# Power_TimerEvents.net
KiCad netlist of a schematic drawn in Altium Designer
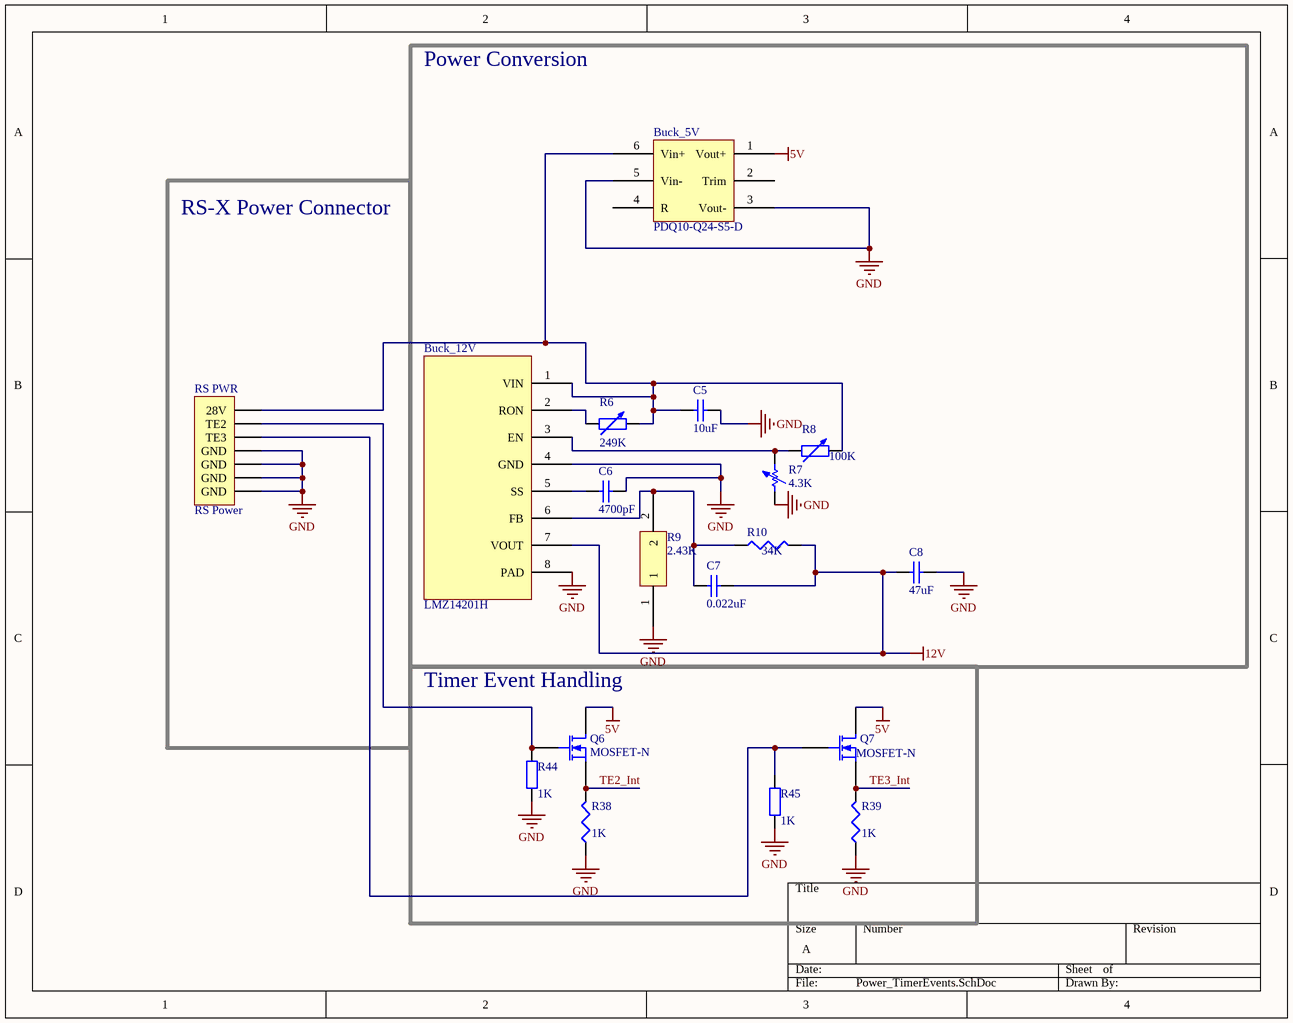
[diagram p0: Power_TimerEvents.SchDoc]

(export (version "E")
  (design (tool "Eeschema 10.0.6"))
  (components
    (comp (ref "Buck_5V")
      (value "PDQ10-Q24-S5-D")
      (footprint "buck_5V")
      (libsource (lib "buck_5V") (part "buck_5V"))
    )
    (comp (ref "Buck_12V")
      (value "LMZ14201H")
      (footprint "LMZ1420")
      (libsource (lib "LMZ1420XX") (part "Component_1"))
    )
    (comp (ref "C5")
      (value "10uF")
      (footprint "C1206")
      (description "Capacitor (Semiconductor SIM Model)")
      (fields (field (name "PUBLISHER") "Altium Limited"))
      (libsource (lib "Miscellaneous Devices") (part "Cap Semi"))
    )
    (comp (ref "C6")
      (value "4700pF")
      (footprint "1608[0603]")
      (description "Capacitor (Semiconductor SIM Model)")
      (fields (field (name "PUBLISHER") "Altium Limited"))
      (libsource (lib "Miscellaneous Devices") (part "Cap Semi"))
    )
    (comp (ref "C7")
      (value "0.022uF")
      (footprint "1608[0603]")
      (description "Capacitor (Semiconductor SIM Model)")
      (fields (field (name "PUBLISHER") "Altium Limited"))
      (libsource (lib "Miscellaneous Devices") (part "Cap Semi"))
    )
    (comp (ref "C8")
      (value "47uF")
      (footprint "C1206")
      (description "Capacitor (Semiconductor SIM Model)")
      (fields (field (name "PUBLISHER") "Altium Limited"))
      (libsource (lib "Miscellaneous Devices") (part "Cap Semi"))
    )
    (comp (ref "Q6")
      (value "MOSFET-N")
      (footprint "E3")
      (description "N-Channel MOSFET")
      (fields (field (name "PUBLISHER") "Altium Limited"))
      (libsource (lib "Miscellaneous Devices") (part "MOSFET-N"))
    )
    (comp (ref "Q7")
      (value "MOSFET-N")
      (footprint "E3")
      (description "N-Channel MOSFET")
      (fields (field (name "PUBLISHER") "Altium Limited"))
      (libsource (lib "Miscellaneous Devices") (part "MOSFET-N"))
    )
    (comp (ref "R6")
      (value "249K")
      (footprint "AXIAL-0.6")
      (description "Variable Resistor")
      (fields (field (name "PUBLISHER") "Altium Limited"))
      (libsource (lib "Miscellaneous Devices") (part "Res Adj2"))
    )
    (comp (ref "R7")
      (value "4.3K")
      (footprint "AXIAL-0.7")
      (description "Variable Resistor")
      (fields (field (name "PUBLISHER") "Altium Limited"))
      (libsource (lib "Miscellaneous Devices") (part "Res Adj1"))
    )
    (comp (ref "R8")
      (value "100K")
      (footprint "AXIAL-0.6")
      (description "Variable Resistor")
      (fields (field (name "PUBLISHER") "Altium Limited"))
      (libsource (lib "Miscellaneous Devices") (part "Res Adj2"))
    )
    (comp (ref "R9") (value "2.43K") (footprint "smd_R9") (libsource (lib "smd_R9_34K") (part "smd_R9")))
    (comp (ref "R10")
      (value "34K")
      (footprint "12Z-2010")
      (description "Resistor")
      (fields (field (name "PUBLISHER") "Altium Limited"))
      (libsource (lib "Miscellaneous Devices") (part "Res3"))
    )
    (comp (ref "R38")
      (value "1K")
      (footprint "J1-0603")
      (description "Resistor")
      (fields (field (name "PUBLISHER") "Altium Limited"))
      (libsource (lib "Miscellaneous Devices") (part "Res3"))
    )
    (comp (ref "R39")
      (value "1K")
      (footprint "J1-0603")
      (description "Resistor")
      (fields (field (name "PUBLISHER") "Altium Limited"))
      (libsource (lib "Miscellaneous Devices") (part "Res3"))
    )
    (comp (ref "R44")
      (value "1K")
      (footprint "AXIAL-0.4")
      (description "Resistor")
      (fields (field (name "PUBLISHER") "Altium Limited"))
      (libsource (lib "Miscellaneous Devices") (part "Res2"))
    )
    (comp (ref "R45")
      (value "1K")
      (footprint "AXIAL-0.4")
      (description "Resistor")
      (fields (field (name "PUBLISHER") "Altium Limited"))
      (libsource (lib "Miscellaneous Devices") (part "Res2"))
    )
    (comp (ref "RS PWR")
      (value "RS Power")
      (footprint "HDR1X7")
      (description "Header, 7-Pin")
      (fields (field (name "PUBLISHER") "Altium Limited"))
      (libsource (lib "Miscellaneous Connectors") (part "Header 7"))
    )
  )
  (nets
    (net (code "1") (name "/TE2_Int") (class "Default")
      (node (ref "Q6") (pin "3") (pinfunction "S_3") (pintype "passive"))
      (node (ref "R38") (pin "2") (pinfunction "2_2") (pintype "passive"))
    )
    (net (code "2") (name "/TE3_Int") (class "Default")
      (node (ref "Q7") (pin "3") (pinfunction "S_3") (pintype "passive"))
      (node (ref "R39") (pin "2") (pinfunction "2_2") (pintype "passive"))
    )
    (net (code "3") (name "5V") (class "Default")
      (node (ref "Buck_5V") (pin "1") (pinfunction "Vout+_1") (pintype "passive"))
      (node (ref "Q6") (pin "1") (pinfunction "D_1") (pintype "passive"))
      (node (ref "Q7") (pin "1") (pinfunction "D_1") (pintype "passive"))
    )
    (net (code "4") (name "12V") (class "Default")
      (node (ref "Buck_12V") (pin "7") (pinfunction "VOUT_7") (pintype "passive"))
      (node (ref "C7") (pin "2") (pinfunction "2_2") (pintype "passive"))
      (node (ref "C8") (pin "1") (pinfunction "1_1") (pintype "passive"))
      (node (ref "R10") (pin "2") (pinfunction "2_2") (pintype "passive"))
    )
    (net (code "5") (name "GND") (class "Default")
      (node (ref "Buck_12V") (pin "4") (pinfunction "GND_4") (pintype "passive"))
      (node (ref "Buck_12V") (pin "8") (pinfunction "PAD_8") (pintype "passive"))
      (node (ref "Buck_5V") (pin "3") (pinfunction "Vout-_3") (pintype "passive"))
      (node (ref "Buck_5V") (pin "5") (pinfunction "Vin-_5") (pintype "passive"))
      (node (ref "C5") (pin "2") (pinfunction "2_2") (pintype "passive"))
      (node (ref "C6") (pin "2") (pinfunction "2_2") (pintype "passive"))
      (node (ref "C8") (pin "2") (pinfunction "2_2") (pintype "passive"))
      (node (ref "R38") (pin "1") (pinfunction "1_1") (pintype "passive"))
      (node (ref "R39") (pin "1") (pinfunction "1_1") (pintype "passive"))
      (node (ref "R44") (pin "1") (pinfunction "1_1") (pintype "passive"))
      (node (ref "R45") (pin "1") (pinfunction "1_1") (pintype "passive"))
      (node (ref "R7") (pin "1") (pinfunction "1_1") (pintype "passive"))
      (node (ref "R9") (pin "1") (pinfunction "1_1") (pintype "passive"))
      (node (ref "RS PWR") (pin "4") (pinfunction "GND_4") (pintype "passive"))
      (node (ref "RS PWR") (pin "5") (pinfunction "GND_5") (pintype "passive"))
      (node (ref "RS PWR") (pin "6") (pinfunction "GND_6") (pintype "passive"))
      (node (ref "RS PWR") (pin "7") (pinfunction "GND_7") (pintype "passive"))
    )
    (net (code "6") (name "Net-(Buck_12V-EN)") (class "Default")
      (node (ref "Buck_12V") (pin "3") (pinfunction "EN_3") (pintype "passive"))
      (node (ref "R7") (pin "2") (pinfunction "2_2") (pintype "passive"))
      (node (ref "R8") (pin "1") (pinfunction "1_1") (pintype "passive"))
    )
    (net (code "7") (name "Net-(Buck_12V-FB)") (class "Default")
      (node (ref "Buck_12V") (pin "6") (pinfunction "FB_6") (pintype "passive"))
      (node (ref "C7") (pin "1") (pinfunction "1_1") (pintype "passive"))
      (node (ref "R10") (pin "1") (pinfunction "1_1") (pintype "passive"))
      (node (ref "R9") (pin "2") (pinfunction "2_2") (pintype "passive"))
    )
    (net (code "8") (name "Net-(Buck_12V-RON)") (class "Default")
      (node (ref "Buck_12V") (pin "2") (pinfunction "RON_2") (pintype "passive"))
      (node (ref "R6") (pin "1") (pinfunction "1_1") (pintype "passive"))
    )
    (net (code "9") (name "Net-(Buck_12V-SS)") (class "Default")
      (node (ref "Buck_12V") (pin "5") (pinfunction "SS_5") (pintype "passive"))
      (node (ref "C6") (pin "1") (pinfunction "1_1") (pintype "passive"))
    )
    (net (code "10") (name "Net-(Buck_12V-VIN)") (class "Default")
      (node (ref "Buck_12V") (pin "1") (pinfunction "VIN_1") (pintype "passive"))
      (node (ref "Buck_5V") (pin "6") (pinfunction "Vin+_6") (pintype "passive"))
      (node (ref "C5") (pin "1") (pinfunction "1_1") (pintype "passive"))
      (node (ref "R6") (pin "2") (pinfunction "2_2") (pintype "passive"))
      (node (ref "R8") (pin "2") (pinfunction "2_2") (pintype "passive"))
      (node (ref "RS PWR") (pin "1") (pinfunction "28V_1") (pintype "passive"))
    )
    (net (code "11") (name "Net-(Q6-G)") (class "Default")
      (node (ref "Q6") (pin "2") (pinfunction "G_2") (pintype "passive"))
      (node (ref "R44") (pin "2") (pinfunction "2_2") (pintype "passive"))
      (node (ref "RS PWR") (pin "2") (pinfunction "TE2_2") (pintype "passive"))
    )
    (net (code "12") (name "Net-(Q7-G)") (class "Default")
      (node (ref "Q7") (pin "2") (pinfunction "G_2") (pintype "passive"))
      (node (ref "R45") (pin "2") (pinfunction "2_2") (pintype "passive"))
      (node (ref "RS PWR") (pin "3") (pinfunction "TE3_3") (pintype "passive"))
    )
    (net (code "13") (name "unconnected-(Buck_5V-R-Pad4)") (class "Default")
      (node (ref "Buck_5V") (pin "4") (pinfunction "R_4") (pintype "passive"))
    )
    (net (code "14") (name "unconnected-(Buck_5V-Trim-Pad2)") (class "Default")
      (node (ref "Buck_5V") (pin "2") (pinfunction "Trim_2") (pintype "passive"))
    )
  )
)
